# AOZ2262AQI-18_SCH.net
KiCad netlist of a schematic drawn in Altium Designer
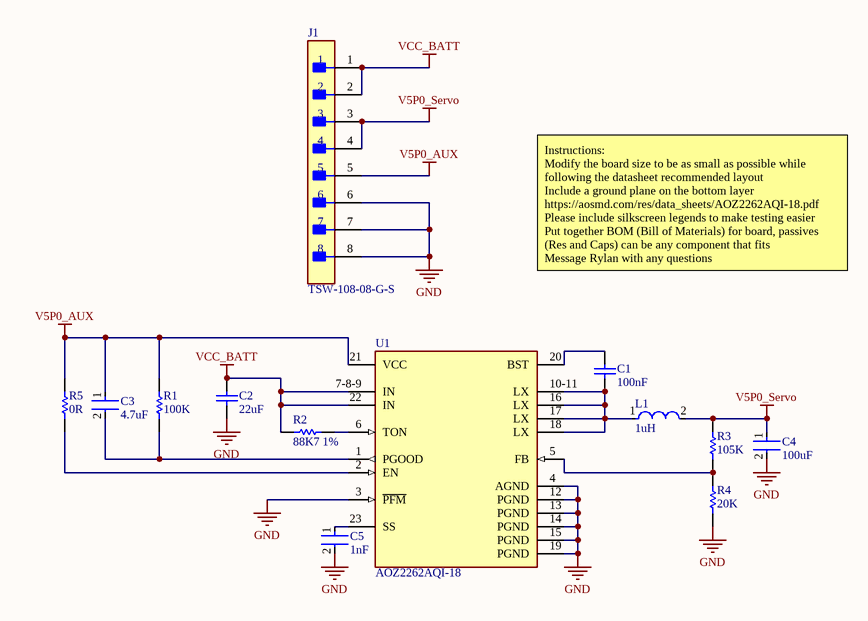
[diagram p0: AOZ2262AQI-18_SCH.SchDoc]

(export (version "E")
  (design (tool "Eeschema 10.0.6"))
  (components
    (comp (ref "C1")
      (value "100nF")
      (footprint "0603")
      (description "CAP 100nF 100V ±10% 0603 (1608 Metric) Thickness 1mm SMD")
      (fields (field (name "TOLERANCE") "Â±10%"))
      (libsource (lib "TAUV-Lib") (part "100nF 0603"))
    )
    (comp (ref "C2")
      (value "22uF")
      (footprint "CAPC1608X100X20ML10")
      (description "Chip Capacitor, 22 uF, +/- 20%, 6.3 V, -55 to 85 degC, 1608 (0603 Metric), RoHS, Tape and Reel")
      (fields
        (field (name "TOLERANCE") "±20%")
        (field (name "PCN PART NUMBER") "MLCCPartNumberChange30/Nov/2012")
      )
      (libsource (lib "Altium Content Vault") (part "CAP-NP-2"))
    )
    (comp (ref "C3")
      (value "4.7uF")
      (footprint "FP-C0603-CG-MFG")
      (description "CAP CER 4.7UF 6.3V X5R 0603")
      (fields (field (name "TOLERANCE") "10%") (field (name "MANUFACTURER") "Kemet"))
      (libsource (lib "Altium Content Vault") (part "11868f565c42a9108669ba33697ecf6"))
    )
    (comp (ref "C4")
      (value "100uF")
      (footprint "FP-C1210C107M9PACTU-MFG")
      (description "CAP CER 100UF 6.3V X5R 1210")
      (fields (field (name "VOLTAGE") "6.3V") (field (name "TOLERANCE") "20%"))
      (libsource (lib "Altium Content Vault") (part "b4654b650e69147ec39a6b967a45e02"))
    )
    (comp (ref "C5")
      (value "1nF")
      (footprint "FP-0603-L_1_6_0_15-W_0_81-IPC_A")
      (description "General Purpose Ceramic Capacitor, 0603, 1nF, 10%, X7R, 15%, 50V")
      (fields (field (name "VOLTAGE") "50V") (field (name "TOLERANCE") "10%"))
      (libsource (lib "Altium Content Vault") (part "02cd4be3c70576c341d710602a673aa"))
    )
    (comp (ref "J1")
      (value "TSW-108-08-G-S")
      (footprint "FP-TSW-108-08-G-S-MFG")
      (description "CONN HEADER VERT 8POS 2.54MM")
      (fields
        (field (name "MANUFACTURER") "Samtec")
        (field (name "OCTOPART") "https://octopart.com/tsw-108-08-g-s-samtec-272653")
      )
      (libsource (lib "Altium Content Vault") (part "99ec2b232beb5d2356d4d77f6a047f0"))
    )
    (comp (ref "L1")
      (value "1uH")
      (footprint "FP-IHLP-4040DZ-FP_3_175x4-MFG")
      (description "Commercial Inductors, Low DCR Series 1uH 25A 2.5mΩ 20%\r\nIHLP4040DZER1R0M11")
      (fields (field (name "TOLERANCE") "20%"))
      (libsource (lib "Altium Content Vault") (part "725321dda6339637d4d059423bc1c3c"))
    )
    (comp (ref "R1")
      (value "100K")
      (footprint "0603")
      (description "ERJ-3EKF1003V-100k 0603")
      (fields (field (name "PART NUMBER") "ERJ-3EKF1003V") (field (name "MANUFACTURER") "Panasonic"))
      (libsource (lib "TAUV-Lib") (part "100K 0603"))
    )
    (comp (ref "R2")
      (value "88K7 1%")
      (footprint "0603")
      (description "88K7 0.1W 1% 0603 (1608 Metric)  SMD")
      (fields (field (name "TOLERANCE") "1 %") (field (name "POWER") "0.1 W"))
      (libsource (lib "TAUV-Lib") (part "88K7 0603"))
    )
    (comp (ref "R3")
      (value "105K")
      (footprint "RESC1608X55X30NL15T15")
      (description "ERJ-3EKF1053V\r\n105K 0603")
      (fields (field (name "PART NUMBER") "ERJ-3EKF1053V") (field (name "MANUFACTURER") "Panasonic"))
      (libsource (lib "Altium Content Vault") (part "RES"))
    )
    (comp (ref "R4")
      (value "20K")
      (footprint "RESC1609X50X30ML10T20")
      (description "CRCW060320K0FKEB\r\n20K 0603")
      (fields (field (name "PART NUMBER") "CRCW060320K0FKEB") (field (name "MANUFACTURER") "Vishay Dale"))
      (libsource (lib "Altium Content Vault") (part "RES"))
    )
    (comp (ref "R5")
      (value "0R")
      (footprint "RESC2013X60X35ML10T20")
      (fields (field (name "TOLERANCE") "5%") (field (name "MANUFACTURER") "Yageo"))
      (libsource (lib "Altium Content Vault") (part "RES-2"))
    )
    (comp (ref "U1")
      (value "AOZ2262AQI-18")
      (footprint "FP-QFN4x4B_23L_EP2_S-MFG")
      (description "POWER IC EZBUCK")
      (libsource (lib "Altium Content Vault") (part "b4377478dbd0c7710c9a3f2ea8715d7"))
    )
  )
  (nets
    (net (code "1") (name "GND") (class "Default")
      (node (ref "C2") (pin "2") (pinfunction "2_2") (pintype "passive"))
      (node (ref "C4") (pin "2") (pinfunction "2_2") (pintype "passive"))
      (node (ref "C5") (pin "2") (pinfunction "2_2") (pintype "passive"))
      (node (ref "J1") (pin "6") (pinfunction "6_6") (pintype "passive"))
      (node (ref "J1") (pin "7") (pinfunction "7_7") (pintype "passive"))
      (node (ref "J1") (pin "8") (pinfunction "8_8") (pintype "passive"))
      (node (ref "R4") (pin "1") (pinfunction "1_1") (pintype "passive"))
      (node (ref "U1") (pin "12") (pinfunction "PGND_12") (pintype "power_in"))
      (node (ref "U1") (pin "13") (pinfunction "PGND_13") (pintype "power_in"))
      (node (ref "U1") (pin "14") (pinfunction "PGND_14") (pintype "power_in"))
      (node (ref "U1") (pin "15") (pinfunction "PGND_15") (pintype "power_in"))
      (node (ref "U1") (pin "19") (pinfunction "PGND_19") (pintype "power_in"))
      (node (ref "U1") (pin "3") (pinfunction "~{PFM}_3") (pintype "input"))
      (node (ref "U1") (pin "4") (pinfunction "AGND_4") (pintype "power_in"))
    )
    (net (code "2") (name "Net-(C1-Pad1)") (class "Default")
      (node (ref "C1") (pin "1") (pinfunction "1_1") (pintype "passive"))
      (node (ref "L1") (pin "1") (pinfunction "1_1") (pintype "passive"))
      (node (ref "U1") (pin "10-11") (pinfunction "LX_10-11") (pintype "passive"))
      (node (ref "U1") (pin "16") (pinfunction "LX_16") (pintype "passive"))
      (node (ref "U1") (pin "17") (pinfunction "LX_17") (pintype "passive"))
      (node (ref "U1") (pin "18") (pinfunction "LX_18") (pintype "passive"))
    )
    (net (code "3") (name "Net-(U1-BST)") (class "Default")
      (node (ref "C1") (pin "2") (pinfunction "2_2") (pintype "passive"))
      (node (ref "U1") (pin "20") (pinfunction "BST_20") (pintype "passive"))
    )
    (net (code "4") (name "Net-(U1-EN)") (class "Default")
      (node (ref "R5") (pin "1") (pinfunction "1_1") (pintype "passive"))
      (node (ref "U1") (pin "2") (pinfunction "EN_2") (pintype "input"))
    )
    (net (code "5") (name "Net-(U1-FB)") (class "Default")
      (node (ref "R3") (pin "1") (pinfunction "1_1") (pintype "passive"))
      (node (ref "R4") (pin "2") (pinfunction "2_2") (pintype "passive"))
      (node (ref "U1") (pin "5") (pinfunction "FB_5") (pintype "input"))
    )
    (net (code "6") (name "Net-(U1-PGOOD)") (class "Default")
      (node (ref "C3") (pin "2") (pinfunction "2_2") (pintype "passive"))
      (node (ref "R1") (pin "2") (pinfunction "2_2") (pintype "passive"))
      (node (ref "U1") (pin "1") (pinfunction "PGOOD_1") (pintype "output"))
    )
    (net (code "7") (name "Net-(U1-SS)") (class "Default")
      (node (ref "C5") (pin "1") (pinfunction "1_1") (pintype "passive"))
      (node (ref "U1") (pin "23") (pinfunction "SS_23") (pintype "passive"))
    )
    (net (code "8") (name "Net-(U1-TON)") (class "Default")
      (node (ref "R2") (pin "2") (pinfunction "2_2") (pintype "passive"))
      (node (ref "U1") (pin "6") (pinfunction "TON_6") (pintype "input"))
    )
    (net (code "9") (name "V5P0_AUX") (class "Default")
      (node (ref "C3") (pin "1") (pinfunction "1_1") (pintype "passive"))
      (node (ref "J1") (pin "5") (pinfunction "5_5") (pintype "passive"))
      (node (ref "R1") (pin "1") (pinfunction "1_1") (pintype "passive"))
      (node (ref "R5") (pin "2") (pinfunction "2_2") (pintype "passive"))
      (node (ref "U1") (pin "21") (pinfunction "VCC_21") (pintype "power_in"))
    )
    (net (code "10") (name "V5P0_Servo") (class "Default")
      (node (ref "C4") (pin "1") (pinfunction "1_1") (pintype "passive"))
      (node (ref "J1") (pin "3") (pinfunction "3_3") (pintype "passive"))
      (node (ref "J1") (pin "4") (pinfunction "4_4") (pintype "passive"))
      (node (ref "L1") (pin "2") (pinfunction "2_2") (pintype "passive"))
      (node (ref "R3") (pin "2") (pinfunction "2_2") (pintype "passive"))
    )
    (net (code "11") (name "VCC_BATT") (class "Default")
      (node (ref "C2") (pin "1") (pinfunction "1_1") (pintype "passive"))
      (node (ref "J1") (pin "1") (pinfunction "1_1") (pintype "passive"))
      (node (ref "J1") (pin "2") (pinfunction "2_2") (pintype "passive"))
      (node (ref "R2") (pin "1") (pinfunction "1_1") (pintype "passive"))
      (node (ref "U1") (pin "22") (pinfunction "IN_22") (pintype "power_in"))
      (node (ref "U1") (pin "7-8-9") (pinfunction "IN_7-8-9") (pintype "power_in"))
    )
  )
)
